# usbDac.net
KiCad netlist of a schematic drawn in EAGLE
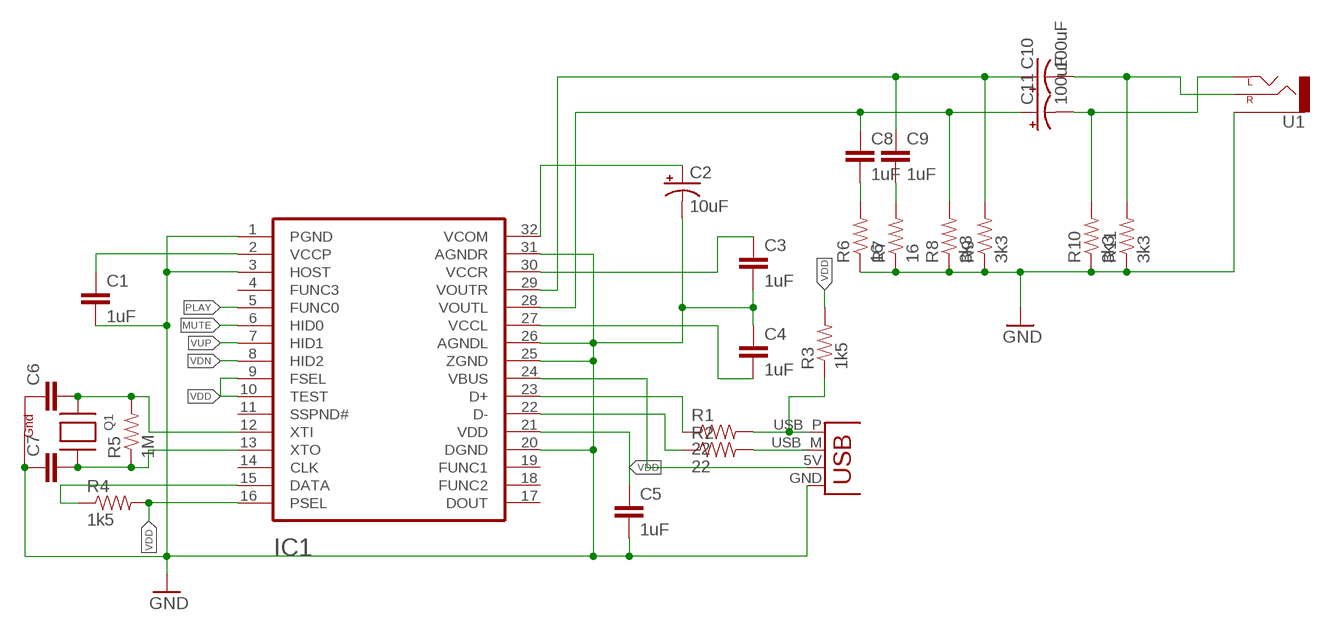
[diagram p0: schematic, sheet 1]

(export (version "E")
  (design (tool "Eeschema 10.0.6"))
  (components
    (comp (ref "C1")
      (value "1uF")
      (footprint "eagle-import:0402-CAP")
      (libsource (lib "eagle-import") (part "CAP0402-CAP"))
    )
    (comp (ref "C2")
      (value "10uF")
      (footprint "eagle-import:EIA3216")
      (libsource (lib "eagle-import") (part "CAP_POL1206"))
    )
    (comp (ref "C3")
      (value "1uF")
      (footprint "eagle-import:0402-CAP")
      (libsource (lib "eagle-import") (part "CAP0402-CAP"))
    )
    (comp (ref "C4")
      (value "1uF")
      (footprint "eagle-import:0402-CAP")
      (libsource (lib "eagle-import") (part "CAP0402-CAP"))
    )
    (comp (ref "C5")
      (value "1uF")
      (footprint "eagle-import:0402-CAP")
      (libsource (lib "eagle-import") (part "CAP0402-CAP"))
    )
    (comp (ref "C6")
      (value "CAP0402-CAP")
      (footprint "eagle-import:0402-CAP")
      (libsource (lib "eagle-import") (part "CAP0402-CAP"))
    )
    (comp (ref "C7")
      (value "CAP0402-CAP")
      (footprint "eagle-import:0402-CAP")
      (libsource (lib "eagle-import") (part "CAP0402-CAP"))
    )
    (comp (ref "C8")
      (value "1uF")
      (footprint "eagle-import:0402-CAP")
      (libsource (lib "eagle-import") (part "CAP0402-CAP"))
    )
    (comp (ref "C9")
      (value "1uF")
      (footprint "eagle-import:0402-CAP")
      (libsource (lib "eagle-import") (part "CAP0402-CAP"))
    )
    (comp (ref "C10")
      (value "100uF")
      (footprint "eagle-import:EIA6032")
      (libsource (lib "eagle-import") (part "CAP_POL6032"))
    )
    (comp (ref "C11")
      (value "100uF")
      (footprint "eagle-import:EIA6032")
      (libsource (lib "eagle-import") (part "CAP_POL6032"))
    )
    (comp (ref "IC1")
      (value "PCM2706")
      (footprint "eagle-import:TQFP32")
      (libsource (lib "eagle-import") (part "PCM2706"))
    )
    (comp (ref "Q1")
      (value "XTAL-4-3225")
      (footprint "eagle-import:NX3225")
      (libsource (lib "eagle-import") (part "XTAL-4-3225"))
    )
    (comp (ref "R1")
      (value "22")
      (footprint "eagle-import:0402-RES")
      (libsource (lib "eagle-import") (part "RESISTOR0402-RES"))
    )
    (comp (ref "R2")
      (value "22")
      (footprint "eagle-import:0402-RES")
      (libsource (lib "eagle-import") (part "RESISTOR0402-RES"))
    )
    (comp (ref "R3")
      (value "1k5")
      (footprint "eagle-import:0402-RES")
      (libsource (lib "eagle-import") (part "RESISTOR0402-RES"))
    )
    (comp (ref "R4")
      (value "1k5")
      (footprint "eagle-import:0402-RES")
      (libsource (lib "eagle-import") (part "RESISTOR0402-RES"))
    )
    (comp (ref "R5")
      (value "1M")
      (footprint "eagle-import:0402-RES")
      (libsource (lib "eagle-import") (part "RESISTOR0402-RES"))
    )
    (comp (ref "R6")
      (value "16")
      (footprint "eagle-import:0402-RES")
      (libsource (lib "eagle-import") (part "RESISTOR0402-RES"))
    )
    (comp (ref "R7")
      (value "16")
      (footprint "eagle-import:0402-RES")
      (libsource (lib "eagle-import") (part "RESISTOR0402-RES"))
    )
    (comp (ref "R8")
      (value "3k3")
      (footprint "eagle-import:0402-RES")
      (libsource (lib "eagle-import") (part "RESISTOR0402-RES"))
    )
    (comp (ref "R9")
      (value "3k3")
      (footprint "eagle-import:0402-RES")
      (libsource (lib "eagle-import") (part "RESISTOR0402-RES"))
    )
    (comp (ref "R10")
      (value "3k3")
      (footprint "eagle-import:0402-RES")
      (libsource (lib "eagle-import") (part "RESISTOR0402-RES"))
    )
    (comp (ref "R11")
      (value "3k3")
      (footprint "eagle-import:0402-RES")
      (libsource (lib "eagle-import") (part "RESISTOR0402-RES"))
    )
    (comp (ref "U1")
      (value "AUDIO-JACKSMD2")
      (footprint "eagle-import:AUDIO-JACK-3.5MM-SMD")
      (libsource (lib "eagle-import") (part "AUDIO-JACKSMD2"))
    )
    (comp (ref "X1")
      (value "USBPCB")
      (footprint "eagle-import:USB-A-PCB")
      (libsource (lib "eagle-import") (part "USBPCB"))
    )
  )
  (nets
    (net (code "1") (name "GND") (class "Default")
      (node (ref "C1") (pin "2") (pinfunction "2_2") (pintype "passive"))
      (node (ref "C2") (pin "C") (pinfunction "-_C") (pintype "passive"))
      (node (ref "C3") (pin "2") (pinfunction "2_2") (pintype "passive"))
      (node (ref "C4") (pin "1") (pinfunction "1_1") (pintype "passive"))
      (node (ref "C5") (pin "2") (pinfunction "2_2") (pintype "passive"))
      (node (ref "C7") (pin "1") (pinfunction "1_1") (pintype "passive"))
      (node (ref "IC1") (pin "1") (pinfunction "PGND_1") (pintype "bidirectional"))
      (node (ref "IC1") (pin "20") (pinfunction "DGND_20") (pintype "bidirectional"))
      (node (ref "IC1") (pin "25") (pinfunction "ZGND_25") (pintype "bidirectional"))
      (node (ref "IC1") (pin "26") (pinfunction "AGNDL_26") (pintype "bidirectional"))
      (node (ref "IC1") (pin "3") (pinfunction "HOST_3") (pintype "bidirectional"))
      (node (ref "IC1") (pin "31") (pinfunction "AGNDR_31") (pintype "bidirectional"))
      (node (ref "Q1") (pin "2") (pinfunction "G2_2") (pintype "power_in"))
      (node (ref "R10") (pin "1") (pinfunction "1_1") (pintype "passive"))
      (node (ref "R11") (pin "1") (pinfunction "1_1") (pintype "passive"))
      (node (ref "R6") (pin "1") (pinfunction "1_1") (pintype "passive"))
      (node (ref "R7") (pin "1") (pinfunction "1_1") (pintype "passive"))
      (node (ref "R8") (pin "1") (pinfunction "1_1") (pintype "passive"))
      (node (ref "R9") (pin "1") (pinfunction "1_1") (pintype "passive"))
      (node (ref "U1") (pin "SLEEVE") (pinfunction "SLEEVE_SLEEVE") (pintype "bidirectional"))
      (node (ref "X1") (pin "GND") (pinfunction "GND_GND") (pintype "bidirectional"))
    )
    (net (code "2") (name "MUTE") (class "Default")
      (node (ref "IC1") (pin "6") (pinfunction "HID0_6") (pintype "bidirectional"))
    )
    (net (code "3") (name "Net-(C2-+)") (class "Default")
      (node (ref "C2") (pin "A") (pinfunction "+_A") (pintype "passive"))
      (node (ref "IC1") (pin "32") (pinfunction "VCOM_32") (pintype "bidirectional"))
    )
    (net (code "4") (name "Net-(C8-Pad2)") (class "Default")
      (node (ref "C8") (pin "2") (pinfunction "2_2") (pintype "passive"))
      (node (ref "R6") (pin "2") (pinfunction "2_2") (pintype "passive"))
    )
    (net (code "5") (name "Net-(C9-Pad2)") (class "Default")
      (node (ref "C9") (pin "2") (pinfunction "2_2") (pintype "passive"))
      (node (ref "R7") (pin "2") (pinfunction "2_2") (pintype "passive"))
    )
    (net (code "6") (name "Net-(C10-+)") (class "Default")
      (node (ref "C10") (pin "P$1") (pinfunction "+_P$1") (pintype "passive"))
      (node (ref "C9") (pin "1") (pinfunction "1_1") (pintype "passive"))
      (node (ref "IC1") (pin "29") (pinfunction "VOUTR_29") (pintype "bidirectional"))
      (node (ref "R9") (pin "2") (pinfunction "2_2") (pintype "passive"))
    )
    (net (code "7") (name "Net-(C10--)") (class "Default")
      (node (ref "C10") (pin "P$2") (pinfunction "-_P$2") (pintype "passive"))
      (node (ref "R11") (pin "2") (pinfunction "2_2") (pintype "passive"))
      (node (ref "U1") (pin "RING") (pinfunction "RIGHT_RING") (pintype "bidirectional"))
    )
    (net (code "8") (name "Net-(C11-+)") (class "Default")
      (node (ref "C11") (pin "P$1") (pinfunction "+_P$1") (pintype "passive"))
      (node (ref "C8") (pin "1") (pinfunction "1_1") (pintype "passive"))
      (node (ref "IC1") (pin "28") (pinfunction "VOUTL_28") (pintype "bidirectional"))
      (node (ref "R8") (pin "2") (pinfunction "2_2") (pintype "passive"))
    )
    (net (code "9") (name "Net-(C11--)") (class "Default")
      (node (ref "C11") (pin "P$2") (pinfunction "-_P$2") (pintype "passive"))
      (node (ref "R10") (pin "2") (pinfunction "2_2") (pintype "passive"))
      (node (ref "U1") (pin "TIP") (pinfunction "LEFT_TIP") (pintype "bidirectional"))
    )
    (net (code "10") (name "Net-(IC1-D+)") (class "Default")
      (node (ref "IC1") (pin "23") (pinfunction "D+_23") (pintype "bidirectional"))
      (node (ref "R1") (pin "1") (pinfunction "1_1") (pintype "passive"))
    )
    (net (code "11") (name "Net-(IC1-D-)") (class "Default")
      (node (ref "IC1") (pin "22") (pinfunction "D-_22") (pintype "bidirectional"))
      (node (ref "R2") (pin "1") (pinfunction "1_1") (pintype "passive"))
    )
    (net (code "12") (name "Net-(IC1-DATA)") (class "Default")
      (node (ref "IC1") (pin "15") (pinfunction "DATA_15") (pintype "bidirectional"))
      (node (ref "R4") (pin "1") (pinfunction "1_1") (pintype "passive"))
    )
    (net (code "13") (name "Net-(IC1-VBUS)") (class "Default")
      (node (ref "IC1") (pin "24") (pinfunction "VBUS_24") (pintype "bidirectional"))
      (node (ref "X1") (pin "5V") (pinfunction "VBUS_5V") (pintype "bidirectional"))
    )
    (net (code "14") (name "Net-(IC1-VCCL)") (class "Default")
      (node (ref "C4") (pin "2") (pinfunction "2_2") (pintype "passive"))
      (node (ref "IC1") (pin "27") (pinfunction "VCCL_27") (pintype "bidirectional"))
    )
    (net (code "15") (name "Net-(IC1-VCCP)") (class "Default")
      (node (ref "C1") (pin "1") (pinfunction "1_1") (pintype "passive"))
      (node (ref "IC1") (pin "2") (pinfunction "VCCP_2") (pintype "bidirectional"))
    )
    (net (code "16") (name "Net-(IC1-VCCR)") (class "Default")
      (node (ref "C3") (pin "1") (pinfunction "1_1") (pintype "passive"))
      (node (ref "IC1") (pin "30") (pinfunction "VCCR_30") (pintype "bidirectional"))
    )
    (net (code "17") (name "Net-(IC1-XTI)") (class "Default")
      (node (ref "C6") (pin "2") (pinfunction "2_2") (pintype "passive"))
      (node (ref "IC1") (pin "12") (pinfunction "XTI_12") (pintype "bidirectional"))
      (node (ref "Q1") (pin "1") (pinfunction "X1_1") (pintype "bidirectional"))
      (node (ref "R5") (pin "2") (pinfunction "2_2") (pintype "passive"))
    )
    (net (code "18") (name "Net-(IC1-XTO)") (class "Default")
      (node (ref "C7") (pin "2") (pinfunction "2_2") (pintype "passive"))
      (node (ref "IC1") (pin "13") (pinfunction "XTO_13") (pintype "bidirectional"))
      (node (ref "Q1") (pin "3") (pinfunction "X2_3") (pintype "bidirectional"))
      (node (ref "R5") (pin "1") (pinfunction "1_1") (pintype "passive"))
    )
    (net (code "19") (name "Net-(Q1-G1)") (class "Default")
      (node (ref "C6") (pin "1") (pinfunction "1_1") (pintype "passive"))
      (node (ref "Q1") (pin "4") (pinfunction "G1_4") (pintype "power_in"))
    )
    (net (code "20") (name "Net-(X1-D+)") (class "Default")
      (node (ref "R1") (pin "2") (pinfunction "2_2") (pintype "passive"))
      (node (ref "R3") (pin "1") (pinfunction "1_1") (pintype "passive"))
      (node (ref "X1") (pin "USB_P") (pinfunction "D+_USB_P") (pintype "bidirectional"))
    )
    (net (code "21") (name "Net-(X1-D-)") (class "Default")
      (node (ref "R2") (pin "2") (pinfunction "2_2") (pintype "passive"))
      (node (ref "X1") (pin "USB_M") (pinfunction "D-_USB_M") (pintype "bidirectional"))
    )
    (net (code "22") (name "PLAY") (class "Default")
      (node (ref "IC1") (pin "5") (pinfunction "FUNC0_5") (pintype "bidirectional"))
    )
    (net (code "23") (name "VDD") (class "Default")
      (node (ref "C5") (pin "1") (pinfunction "1_1") (pintype "passive"))
      (node (ref "IC1") (pin "10") (pinfunction "TEST_10") (pintype "bidirectional"))
      (node (ref "IC1") (pin "16") (pinfunction "PSEL_16") (pintype "bidirectional"))
      (node (ref "IC1") (pin "21") (pinfunction "VDD_21") (pintype "bidirectional"))
      (node (ref "IC1") (pin "9") (pinfunction "FSEL_9") (pintype "bidirectional"))
      (node (ref "R3") (pin "2") (pinfunction "2_2") (pintype "passive"))
      (node (ref "R4") (pin "2") (pinfunction "2_2") (pintype "passive"))
    )
    (net (code "24") (name "VDN") (class "Default")
      (node (ref "IC1") (pin "8") (pinfunction "HID2_8") (pintype "bidirectional"))
    )
    (net (code "25") (name "VUP") (class "Default")
      (node (ref "IC1") (pin "7") (pinfunction "HID1_7") (pintype "bidirectional"))
    )
    (net (code "26") (name "unconnected-(IC1-CLK-Pad14)") (class "Default")
      (node (ref "IC1") (pin "14") (pinfunction "CLK_14") (pintype "bidirectional"))
    )
    (net (code "27") (name "unconnected-(IC1-DOUT-Pad17)") (class "Default")
      (node (ref "IC1") (pin "17") (pinfunction "DOUT_17") (pintype "bidirectional"))
    )
    (net (code "28") (name "unconnected-(IC1-FUNC1-Pad19)") (class "Default")
      (node (ref "IC1") (pin "19") (pinfunction "FUNC1_19") (pintype "bidirectional"))
    )
    (net (code "29") (name "unconnected-(IC1-FUNC2-Pad18)") (class "Default")
      (node (ref "IC1") (pin "18") (pinfunction "FUNC2_18") (pintype "bidirectional"))
    )
    (net (code "30") (name "unconnected-(IC1-FUNC3-Pad4)") (class "Default")
      (node (ref "IC1") (pin "4") (pinfunction "FUNC3_4") (pintype "bidirectional"))
    )
    (net (code "31") (name "unconnected-(IC1-SSPND#-Pad11)") (class "Default")
      (node (ref "IC1") (pin "11") (pinfunction "SSPND#_11") (pintype "bidirectional"))
    )
  )
)
